# ST_LINK_V2.net
KiCad netlist of a schematic drawn in Altium Designer
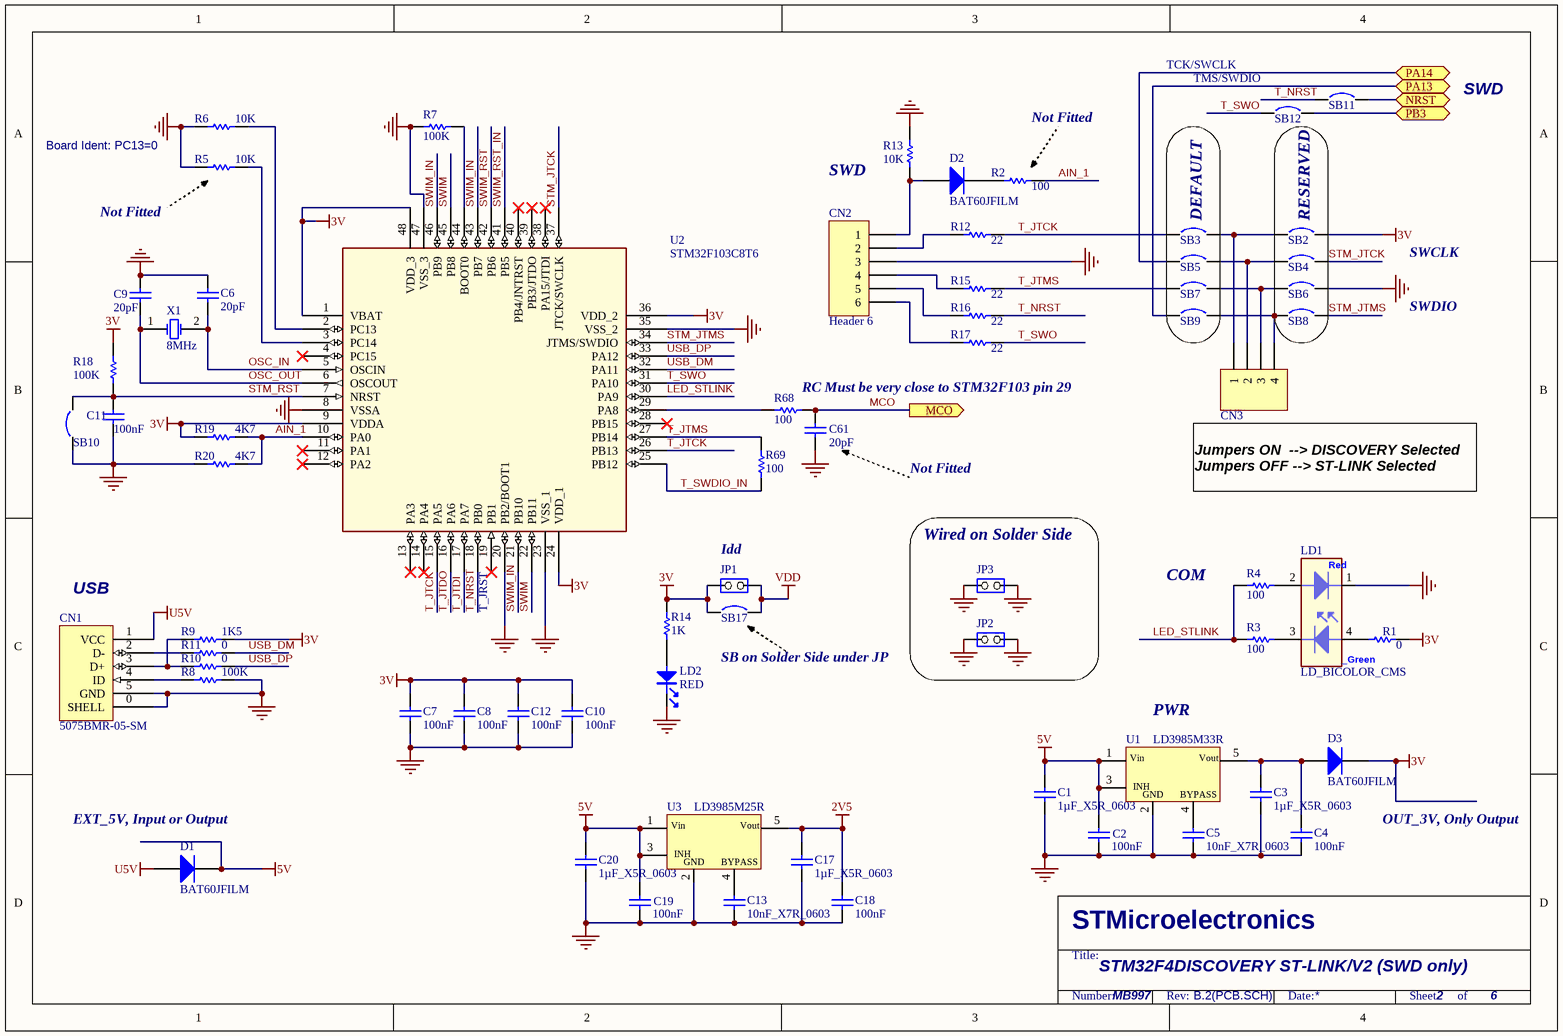
[diagram p0: ST_LINK_V2.SCHDOC]

(export (version "E")
  (design (tool "Eeschema 10.0.6"))
  (components
    (comp (ref "C1")
      (value "1µF_X5R_0603")
      (footprint "0603C")
      (description "0603  X5R 1µF")
      (fields (field (name "TOLERANCE") "10%"))
      (libsource (lib "MB963_1") (part "CAP SMD 0603  X5R 1µF 25V 10%"))
    )
    (comp (ref "C2")
      (value "100nF")
      (footprint "0603C")
      (description "Capacitor")
      (fields (field (name "PUBLISHER") "Altium Limited"))
      (libsource (lib "MB915_1") (part "Cap"))
    )
    (comp (ref "C3")
      (value "1µF_X5R_0603")
      (footprint "0603C")
      (description "0603  X5R 1µF")
      (fields (field (name "TOLERANCE") "10%"))
      (libsource (lib "MB963_1") (part "CAP SMD 0603  X5R 1µF 25V 10%"))
    )
    (comp (ref "C4")
      (value "100nF")
      (footprint "0603C")
      (description "Capacitor")
      (fields (field (name "PUBLISHER") "Altium Limited"))
      (libsource (lib "MB915_1") (part "Cap"))
    )
    (comp (ref "C5")
      (value "10nF_X7R_0603")
      (footprint "0603C")
      (description "0603  X7R 10NF")
      (fields (field (name "TOLERANCE") "10%"))
      (libsource (lib "MB963_1") (part "CAP SMD 0603  X7R 10000PF 50V 10%"))
    )
    (comp (ref "C6")
      (value "20pF")
      (footprint "0402C")
      (description "Capacitor")
      (fields (field (name "PUBLISHER") "Altium Limited"))
      (libsource (lib "MB915_1") (part "Cap"))
    )
    (comp (ref "C7")
      (value "100nF")
      (footprint "0402C")
      (description "Capacitor")
      (fields (field (name "PUBLISHER") "Altium Limited"))
      (libsource (lib "MB915_1") (part "Cap"))
    )
    (comp (ref "C8")
      (value "100nF")
      (footprint "0402C")
      (description "Capacitor")
      (fields (field (name "PUBLISHER") "Altium Limited"))
      (libsource (lib "MB915_1") (part "Cap"))
    )
    (comp (ref "C9")
      (value "20pF")
      (footprint "0402C")
      (description "Capacitor")
      (fields (field (name "PUBLISHER") "Altium Limited"))
      (libsource (lib "MB915_1") (part "Cap"))
    )
    (comp (ref "C10")
      (value "100nF")
      (footprint "0402C")
      (description "Capacitor")
      (fields (field (name "PUBLISHER") "Altium Limited"))
      (libsource (lib "MB915_1") (part "Cap"))
    )
    (comp (ref "C11")
      (value "100nF")
      (footprint "0402C")
      (description "Capacitor")
      (fields (field (name "PUBLISHER") "Altium Limited"))
      (libsource (lib "MB915_1") (part "Cap"))
    )
    (comp (ref "C12")
      (value "100nF")
      (footprint "0402C")
      (description "Capacitor")
      (fields (field (name "PUBLISHER") "Altium Limited"))
      (libsource (lib "MB915_1") (part "Cap"))
    )
    (comp (ref "C13")
      (value "10nF_X7R_0603")
      (footprint "0603C")
      (description "0603  X7R 10NF")
      (fields (field (name "TOLERANCE") "10%"))
      (libsource (lib "MB963_1") (part "CAP SMD 0603  X7R 10000PF 50V 10%"))
    )
    (comp (ref "C17")
      (value "1µF_X5R_0603")
      (footprint "0603C")
      (description "0603  X5R 1µF")
      (fields (field (name "TOLERANCE") "10%"))
      (libsource (lib "MB963_1") (part "CAP SMD 0603  X5R 1µF 25V 10%"))
    )
    (comp (ref "C18")
      (value "100nF")
      (footprint "0603C")
      (description "Capacitor")
      (fields (field (name "PUBLISHER") "Altium Limited"))
      (libsource (lib "MB915_1") (part "Cap"))
    )
    (comp (ref "C19")
      (value "100nF")
      (footprint "0603C")
      (description "Capacitor")
      (fields (field (name "PUBLISHER") "Altium Limited"))
      (libsource (lib "MB915_1") (part "Cap"))
    )
    (comp (ref "C20")
      (value "1µF_X5R_0603")
      (footprint "0603C")
      (description "0603  X5R 1µF")
      (fields (field (name "TOLERANCE") "10%"))
      (libsource (lib "MB963_1") (part "CAP SMD 0603  X5R 1µF 25V 10%"))
    )
    (comp (ref "C61")
      (value "20pF")
      (footprint "0402C")
      (description "Capacitor")
      (fields (field (name "PUBLISHER") "Altium Limited"))
      (libsource (lib "MB915_1") (part "Cap"))
    )
    (comp (ref "CN1")
      (value "5075BMR-05-SM")
      (footprint "USB-MINI-B-SMD")
      (libsource (lib "MB963") (part "USB-MINI-typeB connector"))
    )
    (comp (ref "CN2")
      (value "Header 6")
      (footprint "HDR1X6")
      (description "Header, 6-Pin")
      (fields (field (name "PUBLISHER") "Altium Limited"))
      (libsource (lib "Miscellaneous Connectors") (part "Header 6"))
    )
    (comp (ref "CN3")
      (value "Header 4")
      (footprint "Header 4")
      (description "Header, 4-Pin")
      (fields (field (name "PUBLISHER") "Altium Limited"))
      (libsource (lib "MB963_1") (part "Header 4"))
    )
    (comp (ref "D1")
      (value "BAT60JFILM")
      (footprint "SOD323/A")
      (fields (field (name "PUBLISHER") "Altium Limited"))
      (libsource (lib "MB997") (part "BAT60JFILM"))
    )
    (comp (ref "D2")
      (value "BAT60JFILM")
      (footprint "SOD323/A")
      (fields (field (name "PUBLISHER") "Altium Limited"))
      (libsource (lib "MB997") (part "BAT60JFILM"))
    )
    (comp (ref "D3")
      (value "BAT60JFILM")
      (footprint "SOD323/A")
      (fields (field (name "PUBLISHER") "Altium Limited"))
      (libsource (lib "MB997") (part "BAT60JFILM"))
    )
    (comp (ref "JP1") (value "~") (footprint "SIP2/2.54") (libsource (lib "*") (part "JP2")))
    (comp (ref "JP2") (value "~") (footprint "SIP2/2.54") (libsource (lib "*") (part "JP2")))
    (comp (ref "JP3") (value "~") (footprint "SIP2/2.54") (libsource (lib "*") (part "JP2")))
    (comp (ref "LD1")
      (value "LD_BICOLOR_CMS")
      (footprint "HSMF-A201")
      (description "Bicolor Led")
      (libsource (lib "MB963") (part "LD_BICOLOR_CMS"))
    )
    (comp (ref "LD2") (value "RED") (footprint "0603D") (libsource (lib "MB963_1") (part "PHOTO")))
    (comp (ref "R1")
      (value "0")
      (footprint "0402R")
      (description "Resistor")
      (fields (field (name "PUBLISHER") "Altium Limited"))
      (libsource (lib "MB915_1") (part "res1"))
    )
    (comp (ref "R2")
      (value "100")
      (footprint "0402R")
      (description "Resistor")
      (fields (field (name "PUBLISHER") "Altium Limited"))
      (libsource (lib "MB915_1") (part "res1"))
    )
    (comp (ref "R3")
      (value "100")
      (footprint "0402R")
      (description "Resistor")
      (fields (field (name "PUBLISHER") "Altium Limited"))
      (libsource (lib "MB915_1") (part "res1"))
    )
    (comp (ref "R4")
      (value "100")
      (footprint "0402R")
      (description "Resistor")
      (fields (field (name "PUBLISHER") "Altium Limited"))
      (libsource (lib "MB915_1") (part "res1"))
    )
    (comp (ref "R5")
      (value "10K")
      (footprint "0402R")
      (description "Resistor")
      (fields (field (name "PUBLISHER") "Altium Limited"))
      (libsource (lib "MB915_1") (part "res1"))
    )
    (comp (ref "R6")
      (value "10K")
      (footprint "0402R")
      (description "Resistor")
      (fields (field (name "PUBLISHER") "Altium Limited"))
      (libsource (lib "MB915_1") (part "res1"))
    )
    (comp (ref "R7")
      (value "100K")
      (footprint "0402R")
      (description "Resistor")
      (fields (field (name "PUBLISHER") "Altium Limited"))
      (libsource (lib "MB915_1") (part "res1"))
    )
    (comp (ref "R8")
      (value "100K")
      (footprint "0402R")
      (description "Resistor")
      (fields (field (name "PUBLISHER") "Altium Limited"))
      (libsource (lib "MB915_1") (part "res1"))
    )
    (comp (ref "R9")
      (value "1K5")
      (footprint "0402R")
      (description "Resistor")
      (fields (field (name "PUBLISHER") "Altium Limited"))
      (libsource (lib "MB915_1") (part "res1"))
    )
    (comp (ref "R10")
      (value "0")
      (footprint "0603R")
      (description "Resistor")
      (fields (field (name "PUBLISHER") "Altium Limited"))
      (libsource (lib "MB915_1") (part "res1"))
    )
    (comp (ref "R11")
      (value "0")
      (footprint "0603R")
      (description "Resistor")
      (fields (field (name "PUBLISHER") "Altium Limited"))
      (libsource (lib "MB915_1") (part "res1"))
    )
    (comp (ref "R12")
      (value "22")
      (footprint "0402R")
      (description "Resistor")
      (fields (field (name "PUBLISHER") "Altium Limited"))
      (libsource (lib "MB915_1") (part "res1"))
    )
    (comp (ref "R13")
      (value "10K")
      (footprint "0402R")
      (description "Resistor")
      (fields (field (name "PUBLISHER") "Altium Limited"))
      (libsource (lib "MB915_1") (part "res1"))
    )
    (comp (ref "R14")
      (value "1K")
      (footprint "0402R")
      (description "Resistor")
      (fields (field (name "PUBLISHER") "Altium Limited"))
      (libsource (lib "MB915_1") (part "res1"))
    )
    (comp (ref "R15")
      (value "22")
      (footprint "0402R")
      (description "Resistor")
      (fields (field (name "PUBLISHER") "Altium Limited"))
      (libsource (lib "MB915_1") (part "res1"))
    )
    (comp (ref "R16")
      (value "22")
      (footprint "0402R")
      (description "Resistor")
      (fields (field (name "PUBLISHER") "Altium Limited"))
      (libsource (lib "MB915_1") (part "res1"))
    )
    (comp (ref "R17")
      (value "22")
      (footprint "0402R")
      (description "Resistor")
      (fields (field (name "PUBLISHER") "Altium Limited"))
      (libsource (lib "MB915_1") (part "res1"))
    )
    (comp (ref "R18")
      (value "100K")
      (footprint "0402R")
      (description "Resistor")
      (fields (field (name "PUBLISHER") "Altium Limited"))
      (libsource (lib "MB915_1") (part "res1"))
    )
    (comp (ref "R19")
      (value "4K7")
      (footprint "0402R")
      (description "Resistor")
      (fields (field (name "PUBLISHER") "Altium Limited"))
      (libsource (lib "MB915_1") (part "res1"))
    )
    (comp (ref "R20")
      (value "4K7")
      (footprint "0402R")
      (description "Resistor")
      (fields (field (name "PUBLISHER") "Altium Limited"))
      (libsource (lib "MB915_1") (part "res1"))
    )
    (comp (ref "R68")
      (value "100")
      (footprint "0402R")
      (description "Resistor")
      (fields (field (name "PUBLISHER") "Altium Limited"))
      (libsource (lib "MB915_1") (part "res1"))
    )
    (comp (ref "R69")
      (value "100")
      (footprint "0402R")
      (description "Resistor")
      (fields (field (name "PUBLISHER") "Altium Limited"))
      (libsource (lib "MB915_1") (part "res1"))
    )
    (comp (ref "SB2")
      (value "Circuit Breaker")
      (footprint "JP2_SMD")
      (fields (field (name "PUBLISHER") "Altium Limited"))
      (libsource (lib "MB915") (part "Circuit Breaker"))
    )
    (comp (ref "SB3")
      (value "Circuit Breaker")
      (footprint "JP2_SMD")
      (fields (field (name "PUBLISHER") "Altium Limited"))
      (libsource (lib "MB915") (part "Circuit Breaker"))
    )
    (comp (ref "SB4")
      (value "Circuit Breaker")
      (footprint "JP2_SMD")
      (fields (field (name "PUBLISHER") "Altium Limited"))
      (libsource (lib "MB915") (part "Circuit Breaker"))
    )
    (comp (ref "SB5")
      (value "Circuit Breaker")
      (footprint "JP2_SMD")
      (fields (field (name "PUBLISHER") "Altium Limited"))
      (libsource (lib "MB915") (part "Circuit Breaker"))
    )
    (comp (ref "SB6")
      (value "Circuit Breaker")
      (footprint "JP2_SMD")
      (fields (field (name "PUBLISHER") "Altium Limited"))
      (libsource (lib "MB915") (part "Circuit Breaker"))
    )
    (comp (ref "SB7")
      (value "Circuit Breaker")
      (footprint "JP2_SMD")
      (fields (field (name "PUBLISHER") "Altium Limited"))
      (libsource (lib "MB915") (part "Circuit Breaker"))
    )
    (comp (ref "SB8")
      (value "Circuit Breaker")
      (footprint "JP2_SMD")
      (fields (field (name "PUBLISHER") "Altium Limited"))
      (libsource (lib "MB915") (part "Circuit Breaker"))
    )
    (comp (ref "SB9")
      (value "Circuit Breaker")
      (footprint "JP2_SMD")
      (fields (field (name "PUBLISHER") "Altium Limited"))
      (libsource (lib "MB915") (part "Circuit Breaker"))
    )
    (comp (ref "SB10")
      (value "Circuit Breaker")
      (footprint "JP2_SMD")
      (fields (field (name "PUBLISHER") "Altium Limited"))
      (libsource (lib "MB915") (part "Circuit Breaker"))
    )
    (comp (ref "SB11")
      (value "Circuit Breaker")
      (footprint "JP2_SMD")
      (fields (field (name "PUBLISHER") "Altium Limited"))
      (libsource (lib "MB915") (part "Circuit Breaker"))
    )
    (comp (ref "SB12")
      (value "Circuit Breaker")
      (footprint "JP2_SMD")
      (fields (field (name "PUBLISHER") "Altium Limited"))
      (libsource (lib "MB915") (part "Circuit Breaker"))
    )
    (comp (ref "SB17")
      (value "Circuit Breaker")
      (footprint "JP2_SMD")
      (fields (field (name "PUBLISHER") "Altium Limited"))
      (libsource (lib "MB915") (part "Circuit Breaker"))
    )
    (comp (ref "U1")
      (value "LD3985M33R")
      (footprint "SOT-23-5L")
      (description "Ultra low drop-low noise BiCMOS voltage, regulators low ESR capacitors compatible")
      (libsource (lib "MB997") (part "LD3985M33R"))
    )
    (comp (ref "U2")
      (value "STM32F103C8T6")
      (footprint "QFP48 7X7")
      (libsource (lib "MB963") (part "STM32F103C8T6"))
    )
    (comp (ref "U3")
      (value "LD3985M25R")
      (footprint "SOT-23-5L")
      (description "Ultra low drop-low noise BiCMOS voltage, regulators low ESR capacitors compatible")
      (libsource (lib "MB997") (part "LD3985M25R"))
    )
    (comp (ref "X1")
      (value "8MHz")
      (footprint "XTAL1")
      (description "Crystal Oscillator")
      (fields (field (name "PUBLISHER") "Altium Limited"))
      (libsource (lib "MB963_1") (part "XTAL"))
    )
  )
  (nets
    (net (code "1") (name "/AIN_1") (class "Default")
      (node (ref "R19") (pin "2") (pinfunction "2_2") (pintype "passive"))
      (node (ref "R2") (pin "2") (pinfunction "2_2") (pintype "passive"))
      (node (ref "R20") (pin "2") (pinfunction "2_2") (pintype "passive"))
      (node (ref "U2") (pin "10") (pinfunction "PA0_10") (pintype "bidirectional"))
    )
    (net (code "2") (name "/LED_STLINK") (class "Default")
      (node (ref "R3") (pin "1") (pinfunction "1_1") (pintype "passive"))
      (node (ref "R4") (pin "1") (pinfunction "1_1") (pintype "passive"))
      (node (ref "U2") (pin "30") (pinfunction "PA9_30") (pintype "bidirectional"))
    )
    (net (code "3") (name "/MCO") (class "Default")
      (node (ref "C61") (pin "1") (pinfunction "1_1") (pintype "passive"))
      (node (ref "R68") (pin "2") (pinfunction "2_2") (pintype "passive"))
    )
    (net (code "4") (name "/NRST") (class "Default")
      (node (ref "SB11") (pin "2") (pinfunction "2_2") (pintype "passive"))
    )
    (net (code "5") (name "/OSC_IN") (class "Default")
      (node (ref "C6") (pin "2") (pinfunction "2_2") (pintype "passive"))
      (node (ref "U2") (pin "5") (pinfunction "OSCIN_5") (pintype "input"))
      (node (ref "X1") (pin "2") (pinfunction "OSC2_2") (pintype "passive"))
    )
    (net (code "6") (name "/OSC_OUT") (class "Default")
      (node (ref "C9") (pin "2") (pinfunction "2_2") (pintype "passive"))
      (node (ref "U2") (pin "6") (pinfunction "OSCOUT_6") (pintype "output"))
      (node (ref "X1") (pin "1") (pinfunction "OSC1_1") (pintype "passive"))
    )
    (net (code "7") (name "/PA13") (class "Default")
      (node (ref "SB9") (pin "1") (pinfunction "1_1") (pintype "passive"))
    )
    (net (code "8") (name "/PA14") (class "Default")
      (node (ref "SB5") (pin "1") (pinfunction "1_1") (pintype "passive"))
    )
    (net (code "9") (name "/PB3") (class "Default")
      (node (ref "SB12") (pin "2") (pinfunction "2_2") (pintype "passive"))
    )
    (net (code "10") (name "/STM_JTCK") (class "Default")
      (node (ref "SB4") (pin "2") (pinfunction "2_2") (pintype "passive"))
      (node (ref "U2") (pin "37") (pinfunction "JTCK/SWCLK_37") (pintype "bidirectional"))
    )
    (net (code "11") (name "/STM_JTMS") (class "Default")
      (node (ref "SB8") (pin "2") (pinfunction "2_2") (pintype "passive"))
      (node (ref "U2") (pin "34") (pinfunction "JTMS/SWDIO_34") (pintype "bidirectional"))
    )
    (net (code "12") (name "/STM_RST") (class "Default")
      (node (ref "C11") (pin "2") (pinfunction "2_2") (pintype "passive"))
      (node (ref "R18") (pin "1") (pinfunction "1_1") (pintype "passive"))
      (node (ref "SB10") (pin "2") (pinfunction "2_2") (pintype "passive"))
      (node (ref "U2") (pin "7") (pinfunction "NRST_7") (pintype "input"))
    )
    (net (code "13") (name "/SWIM") (class "Default")
      (node (ref "U2") (pin "22") (pinfunction "PB11_22") (pintype "bidirectional"))
      (node (ref "U2") (pin "45") (pinfunction "PB8_45") (pintype "bidirectional"))
    )
    (net (code "14") (name "/SWIM_IN") (class "Default")
      (node (ref "U2") (pin "21") (pinfunction "PB10_21") (pintype "bidirectional"))
      (node (ref "U2") (pin "43") (pinfunction "PB7_43") (pintype "bidirectional"))
      (node (ref "U2") (pin "46") (pinfunction "PB9_46") (pintype "bidirectional"))
    )
    (net (code "15") (name "/SWIM_RST") (class "Default")
      (node (ref "U2") (pin "42") (pinfunction "PB6_42") (pintype "bidirectional"))
    )
    (net (code "16") (name "/SWIM_RST_IN") (class "Default")
      (node (ref "U2") (pin "41") (pinfunction "PB5_41") (pintype "bidirectional"))
    )
    (net (code "17") (name "/T_JTCK") (class "Default")
      (node (ref "R12") (pin "2") (pinfunction "2_2") (pintype "passive"))
      (node (ref "SB3") (pin "1") (pinfunction "1_1") (pintype "passive"))
      (node (ref "U2") (pin "15") (pinfunction "PA5_15") (pintype "bidirectional"))
      (node (ref "U2") (pin "26") (pinfunction "PB13_26") (pintype "bidirectional"))
    )
    (net (code "18") (name "/T_JTDI") (class "Default")
      (node (ref "U2") (pin "17") (pinfunction "PA7_17") (pintype "bidirectional"))
    )
    (net (code "19") (name "/T_JTDO") (class "Default")
      (node (ref "U2") (pin "16") (pinfunction "PA6_16") (pintype "bidirectional"))
    )
    (net (code "20") (name "/T_JTMS") (class "Default")
      (node (ref "R15") (pin "2") (pinfunction "2_2") (pintype "passive"))
      (node (ref "R69") (pin "2") (pinfunction "2_2") (pintype "passive"))
      (node (ref "SB7") (pin "1") (pinfunction "1_1") (pintype "passive"))
      (node (ref "U2") (pin "27") (pinfunction "PB14_27") (pintype "bidirectional"))
    )
    (net (code "21") (name "/T_NRST") (class "Default")
      (node (ref "R16") (pin "2") (pinfunction "2_2") (pintype "passive"))
      (node (ref "SB11") (pin "1") (pinfunction "1_1") (pintype "passive"))
      (node (ref "U2") (pin "18") (pinfunction "PB0_18") (pintype "bidirectional"))
    )
    (net (code "22") (name "/T_SWDIO_IN") (class "Default")
      (node (ref "R69") (pin "1") (pinfunction "1_1") (pintype "passive"))
      (node (ref "U2") (pin "25") (pinfunction "PB12_25") (pintype "bidirectional"))
    )
    (net (code "23") (name "/T_SWO") (class "Default")
      (node (ref "R17") (pin "2") (pinfunction "2_2") (pintype "passive"))
      (node (ref "SB12") (pin "1") (pinfunction "1_1") (pintype "passive"))
      (node (ref "U2") (pin "31") (pinfunction "PA10_31") (pintype "bidirectional"))
    )
    (net (code "24") (name "/USB_DM") (class "Default")
      (node (ref "R11") (pin "2") (pinfunction "2_2") (pintype "passive"))
      (node (ref "U2") (pin "32") (pinfunction "PA11_32") (pintype "bidirectional"))
    )
    (net (code "25") (name "/USB_DP") (class "Default")
      (node (ref "R10") (pin "2") (pinfunction "2_2") (pintype "passive"))
      (node (ref "U2") (pin "33") (pinfunction "PA12_33") (pintype "bidirectional"))
    )
    (net (code "26") (name "2V5") (class "Default")
      (node (ref "C17") (pin "1") (pinfunction "1_1") (pintype "passive"))
      (node (ref "C18") (pin "2") (pinfunction "2_2") (pintype "passive"))
      (node (ref "U3") (pin "5") (pinfunction "Vout_5") (pintype "passive"))
    )
    (net (code "27") (name "3V") (class "Default")
      (node (ref "C10") (pin "2") (pinfunction "2_2") (pintype "passive"))
      (node (ref "C12") (pin "1") (pinfunction "1_1") (pintype "passive"))
      (node (ref "C7") (pin "2") (pinfunction "2_2") (pintype "passive"))
      (node (ref "C8") (pin "2") (pinfunction "2_2") (pintype "passive"))
      (node (ref "D3") (pin "2") (pinfunction "K_2") (pintype "passive"))
      (node (ref "JP1") (pin "1") (pinfunction "COMMON_1") (pintype "passive"))
      (node (ref "R1") (pin "2") (pinfunction "2_2") (pintype "passive"))
      (node (ref "R14") (pin "2") (pinfunction "2_2") (pintype "passive"))
      (node (ref "R18") (pin "2") (pinfunction "2_2") (pintype "passive"))
      (node (ref "R19") (pin "1") (pinfunction "1_1") (pintype "passive"))
      (node (ref "R9") (pin "2") (pinfunction "2_2") (pintype "passive"))
      (node (ref "SB17") (pin "1") (pinfunction "1_1") (pintype "passive"))
      (node (ref "SB2") (pin "2") (pinfunction "2_2") (pintype "passive"))
      (node (ref "U2") (pin "1") (pinfunction "VBAT_1") (pintype "power_in"))
      (node (ref "U2") (pin "24") (pinfunction "VDD_1_24") (pintype "power_in"))
      (node (ref "U2") (pin "36") (pinfunction "VDD_2_36") (pintype "power_in"))
      (node (ref "U2") (pin "48") (pinfunction "VDD_3_48") (pintype "power_in"))
      (node (ref "U2") (pin "9") (pinfunction "VDDA_9") (pintype "power_in"))
    )
    (net (code "28") (name "5V") (class "Default")
      (node (ref "C1") (pin "2") (pinfunction "2_2") (pintype "passive"))
      (node (ref "C19") (pin "2") (pinfunction "2_2") (pintype "passive"))
      (node (ref "C2") (pin "2") (pinfunction "2_2") (pintype "passive"))
      (node (ref "C20") (pin "2") (pinfunction "2_2") (pintype "passive"))
      (node (ref "D1") (pin "2") (pinfunction "K_2") (pintype "passive"))
      (node (ref "U1") (pin "1") (pinfunction "Vin_1") (pintype "passive"))
      (node (ref "U1") (pin "3") (pinfunction "CE_3") (pintype "passive"))
      (node (ref "U3") (pin "1") (pinfunction "Vin_1") (pintype "passive"))
      (node (ref "U3") (pin "3") (pinfunction "CE_3") (pintype "passive"))
    )
    (net (code "29") (name "GND") (class "Default")
      (node (ref "C1") (pin "1") (pinfunction "1_1") (pintype "passive"))
      (node (ref "C10") (pin "1") (pinfunction "1_1") (pintype "passive"))
      (node (ref "C11") (pin "1") (pinfunction "1_1") (pintype "passive"))
      (node (ref "C12") (pin "2") (pinfunction "2_2") (pintype "passive"))
      (node (ref "C13") (pin "1") (pinfunction "1_1") (pintype "passive"))
      (node (ref "C17") (pin "2") (pinfunction "2_2") (pintype "passive"))
      (node (ref "C18") (pin "1") (pinfunction "1_1") (pintype "passive"))
      (node (ref "C19") (pin "1") (pinfunction "1_1") (pintype "passive"))
      (node (ref "C2") (pin "1") (pinfunction "1_1") (pintype "passive"))
      (node (ref "C20") (pin "1") (pinfunction "1_1") (pintype "passive"))
      (node (ref "C3") (pin "2") (pinfunction "2_2") (pintype "passive"))
      (node (ref "C4") (pin "1") (pinfunction "1_1") (pintype "passive"))
      (node (ref "C5") (pin "1") (pinfunction "1_1") (pintype "passive"))
      (node (ref "C6") (pin "1") (pinfunction "1_1") (pintype "passive"))
      (node (ref "C61") (pin "2") (pinfunction "2_2") (pintype "passive"))
      (node (ref "C7") (pin "1") (pinfunction "1_1") (pintype "passive"))
      (node (ref "C8") (pin "1") (pinfunction "1_1") (pintype "passive"))
      (node (ref "C9") (pin "1") (pinfunction "1_1") (pintype "passive"))
      (node (ref "CN1") (pin "0") (pinfunction "SHELL_0") (pintype "power_in"))
      (node (ref "CN1") (pin "5") (pinfunction "GND_5") (pintype "power_in"))
      (node (ref "CN2") (pin "3") (pinfunction "3_3") (pintype "passive"))
      (node (ref "JP2") (pin "1") (pinfunction "COMMON_1") (pintype "passive"))
      (node (ref "JP2") (pin "2") (pinfunction "NO_2") (pintype "passive"))
      (node (ref "JP3") (pin "1") (pinfunction "COMMON_1") (pintype "passive"))
      (node (ref "JP3") (pin "2") (pinfunction "NO_2") (pintype "passive"))
      (node (ref "LD1") (pin "1") (pinfunction "1_1") (pintype "passive"))
      (node (ref "LD2") (pin "2") (pintype "passive"))
      (node (ref "R13") (pin "2") (pinfunction "2_2") (pintype "passive"))
      (node (ref "R20") (pin "1") (pinfunction "1_1") (pintype "passive"))
      (node (ref "R5") (pin "1") (pinfunction "1_1") (pintype "passive"))
      (node (ref "R6") (pin "1") (pinfunction "1_1") (pintype "passive"))
      (node (ref "R7") (pin "1") (pinfunction "1_1") (pintype "passive"))
      (node (ref "R8") (pin "2") (pinfunction "2_2") (pintype "passive"))
      (node (ref "SB10") (pin "1") (pinfunction "1_1") (pintype "passive"))
      (node (ref "SB6") (pin "2") (pinfunction "2_2") (pintype "passive"))
      (node (ref "U1") (pin "2") (pinfunction "GND_2") (pintype "passive"))
      (node (ref "U2") (pin "20") (pinfunction "PB2/BOOT1_20") (pintype "bidirectional"))
      (node (ref "U2") (pin "23") (pinfunction "VSS_1_23") (pintype "power_in"))
      (node (ref "U2") (pin "35") (pinfunction "VSS_2_35") (pintype "power_in"))
      (node (ref "U2") (pin "47") (pinfunction "VSS_3_47") (pintype "power_in"))
      (node (ref "U2") (pin "8") (pinfunction "VSSA_8") (pintype "power_in"))
      (node (ref "U3") (pin "2") (pinfunction "GND_2") (pintype "passive"))
    )
    (net (code "30") (name "Net-(CN1-D+)") (class "Default")
      (node (ref "CN1") (pin "3") (pinfunction "D+_3") (pintype "bidirectional"))
      (node (ref "R10") (pin "1") (pinfunction "1_1") (pintype "passive"))
      (node (ref "R9") (pin "1") (pinfunction "1_1") (pintype "passive"))
    )
    (net (code "31") (name "Net-(CN1-D-)") (class "Default")
      (node (ref "CN1") (pin "2") (pinfunction "D-_2") (pintype "bidirectional"))
      (node (ref "R11") (pin "1") (pinfunction "1_1") (pintype "passive"))
    )
    (net (code "32") (name "Net-(CN1-ID)") (class "Default")
      (node (ref "CN1") (pin "4") (pinfunction "ID_4") (pintype "input"))
      (node (ref "R8") (pin "1") (pinfunction "1_1") (pintype "passive"))
    )
    (net (code "33") (name "Net-(CN2-Pad2)") (class "Default")
      (node (ref "CN2") (pin "2") (pinfunction "2_2") (pintype "passive"))
      (node (ref "R12") (pin "1") (pinfunction "1_1") (pintype "passive"))
    )
    (net (code "34") (name "Net-(CN2-Pad4)") (class "Default")
      (node (ref "CN2") (pin "4") (pinfunction "4_4") (pintype "passive"))
      (node (ref "R15") (pin "1") (pinfunction "1_1") (pintype "passive"))
    )
    (net (code "35") (name "Net-(CN2-Pad5)") (class "Default")
      (node (ref "CN2") (pin "5") (pinfunction "5_5") (pintype "passive"))
      (node (ref "R16") (pin "1") (pinfunction "1_1") (pintype "passive"))
    )
    (net (code "36") (name "Net-(CN2-Pad6)") (class "Default")
      (node (ref "CN2") (pin "6") (pinfunction "6_6") (pintype "passive"))
      (node (ref "R17") (pin "1") (pinfunction "1_1") (pintype "passive"))
    )
    (net (code "37") (name "Net-(CN3-Pad1)") (class "Default")
      (node (ref "CN3") (pin "1") (pinfunction "1_1") (pintype "passive"))
      (node (ref "SB2") (pin "1") (pinfunction "1_1") (pintype "passive"))
      (node (ref "SB3") (pin "2") (pinfunction "2_2") (pintype "passive"))
    )
    (net (code "38") (name "Net-(CN3-Pad2)") (class "Default")
      (node (ref "CN3") (pin "2") (pinfunction "2_2") (pintype "passive"))
      (node (ref "SB4") (pin "1") (pinfunction "1_1") (pintype "passive"))
      (node (ref "SB5") (pin "2") (pinfunction "2_2") (pintype "passive"))
    )
    (net (code "39") (name "Net-(CN3-Pad3)") (class "Default")
      (node (ref "CN3") (pin "3") (pinfunction "3_3") (pintype "passive"))
      (node (ref "SB6") (pin "1") (pinfunction "1_1") (pintype "passive"))
      (node (ref "SB7") (pin "2") (pinfunction "2_2") (pintype "passive"))
    )
    (net (code "40") (name "Net-(CN3-Pad4)") (class "Default")
      (node (ref "CN3") (pin "4") (pinfunction "4_4") (pintype "passive"))
      (node (ref "SB8") (pin "1") (pinfunction "1_1") (pintype "passive"))
      (node (ref "SB9") (pin "2") (pinfunction "2_2") (pintype "passive"))
    )
    (net (code "41") (name "Net-(D2-A)") (class "Default")
      (node (ref "CN2") (pin "1") (pinfunction "1_1") (pintype "passive"))
      (node (ref "D2") (pin "1") (pinfunction "A_1") (pintype "passive"))
      (node (ref "R13") (pin "1") (pinfunction "1_1") (pintype "passive"))
    )
    (net (code "42") (name "Net-(D2-K)") (class "Default")
      (node (ref "D2") (pin "2") (pinfunction "K_2") (pintype "passive"))
      (node (ref "R2") (pin "1") (pinfunction "1_1") (pintype "passive"))
    )
    (net (code "43") (name "Net-(D3-A)") (class "Default")
      (node (ref "C3") (pin "1") (pinfunction "1_1") (pintype "passive"))
      (node (ref "C4") (pin "2") (pinfunction "2_2") (pintype "passive"))
      (node (ref "D3") (pin "1") (pinfunction "A_1") (pintype "passive"))
      (node (ref "U1") (pin "5") (pinfunction "Vout_5") (pintype "passive"))
    )
    (net (code "44") (name "Net-(LD1-Pad2)") (class "Default")
      (node (ref "LD1") (pin "2") (pinfunction "2_2") (pintype "passive"))
      (node (ref "R4") (pin "2") (pinfunction "2_2") (pintype "passive"))
    )
    (net (code "45") (name "Net-(LD1-Pad3)") (class "Default")
      (node (ref "LD1") (pin "3") (pinfunction "3_3") (pintype "passive"))
      (node (ref "R3") (pin "2") (pinfunction "2_2") (pintype "passive"))
    )
    (net (code "46") (name "Net-(LD1-Pad4)") (class "Default")
      (node (ref "LD1") (pin "4") (pinfunction "4_4") (pintype "passive"))
      (node (ref "R1") (pin "1") (pinfunction "1_1") (pintype "passive"))
    )
    (net (code "47") (name "Net-(LD2-Pad1)") (class "Default")
      (node (ref "LD2") (pin "1") (pintype "passive"))
      (node (ref "R14") (pin "1") (pinfunction "1_1") (pintype "passive"))
    )
    (net (code "48") (name "Net-(U1-BYPASS)") (class "Default")
      (node (ref "C5") (pin "2") (pinfunction "2_2") (pintype "passive"))
      (node (ref "U1") (pin "4") (pinfunction "BYPASS_4") (pintype "passive"))
    )
    (net (code "49") (name "Net-(U2-BOOT0)") (class "Default")
      (node (ref "R7") (pin "2") (pinfunction "2_2") (pintype "passive"))
      (node (ref "U2") (pin "44") (pinfunction "BOOT0_44") (pintype "bidirectional"))
    )
    (net (code "50") (name "Net-(U2-PA8)") (class "Default")
      (node (ref "R68") (pin "1") (pinfunction "1_1") (pintype "passive"))
      (node (ref "U2") (pin "29") (pinfunction "PA8_29") (pintype "bidirectional"))
    )
    (net (code "51") (name "Net-(U2-PC13)") (class "Default")
      (node (ref "R6") (pin "2") (pinfunction "2_2") (pintype "passive"))
      (node (ref "U2") (pin "2") (pinfunction "PC13_2") (pintype "bidirectional"))
    )
    (net (code "52") (name "Net-(U2-PC14)") (class "Default")
      (node (ref "R5") (pin "2") (pinfunction "2_2") (pintype "passive"))
      (node (ref "U2") (pin "3") (pinfunction "PC14_3") (pintype "bidirectional"))
    )
    (net (code "53") (name "Net-(U3-BYPASS)") (class "Default")
      (node (ref "C13") (pin "2") (pinfunction "2_2") (pintype "passive"))
      (node (ref "U3") (pin "4") (pinfunction "BYPASS_4") (pintype "passive"))
    )
    (net (code "54") (name "U5V") (class "Default")
      (node (ref "CN1") (pin "1") (pinfunction "VCC_1") (pintype "power_in"))
      (node (ref "D1") (pin "1") (pinfunction "A_1") (pintype "passive"))
    )
    (net (code "55") (name "VDD") (class "Default")
      (node (ref "JP1") (pin "2") (pinfunction "NO_2") (pintype "passive"))
      (node (ref "SB17") (pin "2") (pinfunction "2_2") (pintype "passive"))
    )
    (net (code "56") (name "unconnected-(U2-PA1-Pad11)") (class "Default")
      (node (ref "U2") (pin "11") (pinfunction "PA1_11") (pintype "bidirectional+no_connect"))
    )
    (net (code "57") (name "unconnected-(U2-PA2-Pad12)") (class "Default")
      (node (ref "U2") (pin "12") (pinfunction "PA2_12") (pintype "bidirectional+no_connect"))
    )
    (net (code "58") (name "unconnected-(U2-PA3-Pad13)") (class "Default")
      (node (ref "U2") (pin "13") (pinfunction "PA3_13") (pintype "bidirectional+no_connect"))
    )
    (net (code "59") (name "unconnected-(U2-PA4-Pad14)") (class "Default")
      (node (ref "U2") (pin "14") (pinfunction "PA4_14") (pintype "bidirectional+no_connect"))
    )
    (net (code "60") (name "unconnected-(U2-PA15{slash}JTDI-Pad38)") (class "Default")
      (node (ref "U2") (pin "38") (pinfunction "PA15/JTDI_38") (pintype "bidirectional+no_connect"))
    )
    (net (code "61") (name "unconnected-(U2-PB1-Pad19)") (class "Default")
      (node (ref "U2") (pin "19") (pinfunction "PB1_19") (pintype "input+no_connect"))
    )
    (net (code "62") (name "unconnected-(U2-PB3{slash}JTDO-Pad39)") (class "Default")
      (node (ref "U2") (pin "39") (pinfunction "PB3/JTDO_39") (pintype "bidirectional+no_connect"))
    )
    (net (code "63") (name "unconnected-(U2-PB4{slash}JNTRST-Pad40)") (class "Default")
      (node (ref "U2") (pin "40") (pinfunction "PB4/JNTRST_40") (pintype "bidirectional+no_connect"))
    )
    (net (code "64") (name "unconnected-(U2-PB15-Pad28)") (class "Default")
      (node (ref "U2") (pin "28") (pinfunction "PB15_28") (pintype "bidirectional+no_connect"))
    )
    (net (code "65") (name "unconnected-(U2-PC15-Pad4)") (class "Default")
      (node (ref "U2") (pin "4") (pinfunction "PC15_4") (pintype "bidirectional+no_connect"))
    )
  )
)
